# Power.net
KiCad netlist of a schematic drawn in Altium Designer
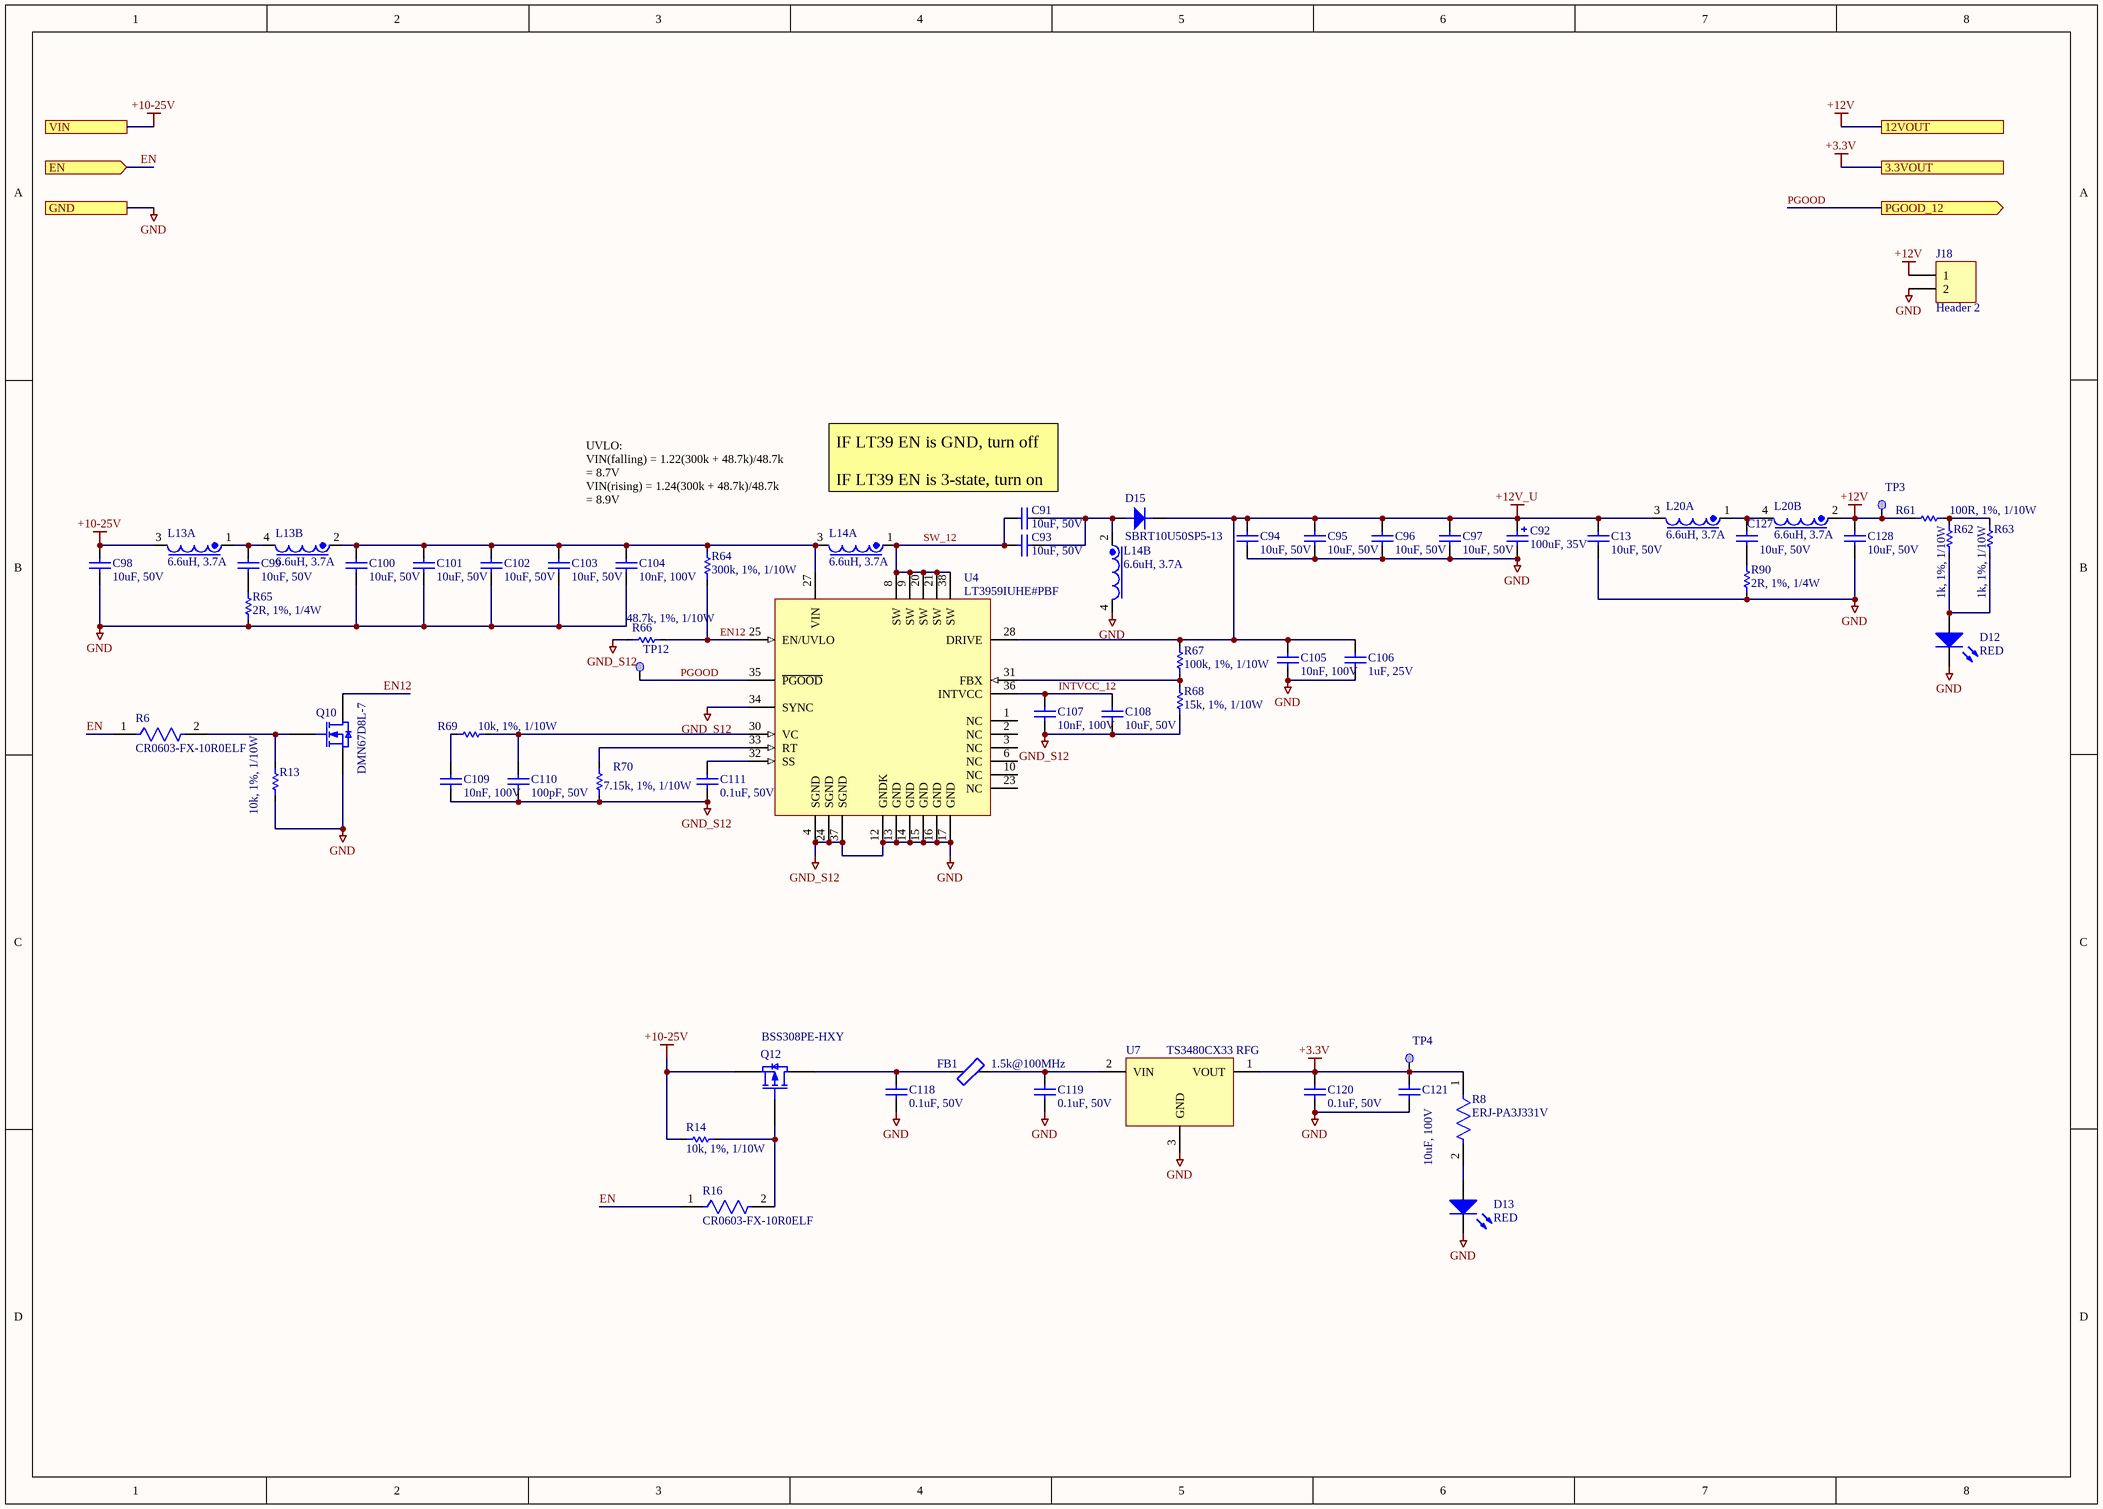
[diagram p0: Power.SchDoc]

(export (version "E")
  (design (tool "Eeschema 10.0.6"))
  (components
    (comp (ref "C13")
      (value "10uF, 50V")
      (footprint "1206")
      (description "CAP CER 10UF 50V X7R 1206")
      (fields (field (name "PART NUMBER") "NS00832"))
      (libsource (lib "FullPartsDB") (part "Cap"))
    )
    (comp (ref "C91")
      (value "10uF, 50V")
      (footprint "1206")
      (description "CAP CER 10UF 50V X7R 1206")
      (fields (field (name "PART NUMBER") "NS00832"))
      (libsource (lib "FullPartsDB") (part "Cap"))
    )
    (comp (ref "C92")
      (value "100uF, 35V")
      (footprint "CAPAE7866X80L")
      (description "CAP ALUM 100UF 20% 35V SMD")
      (fields (field (name "PART NUMBER") "NS00911"))
      (libsource (lib "FullPartsDB") (part "CAP_POL"))
    )
    (comp (ref "C93")
      (value "10uF, 50V")
      (footprint "1206")
      (description "CAP CER 10UF 50V X7R 1206")
      (fields (field (name "PART NUMBER") "NS00832"))
      (libsource (lib "FullPartsDB") (part "Cap"))
    )
    (comp (ref "C94")
      (value "10uF, 50V")
      (footprint "1206")
      (description "CAP CER 10UF 50V X7R 1206")
      (fields (field (name "PART NUMBER") "NS00832"))
      (libsource (lib "FullPartsDB") (part "Cap"))
    )
    (comp (ref "C95")
      (value "10uF, 50V")
      (footprint "1206")
      (description "CAP CER 10UF 50V X7R 1206")
      (fields (field (name "PART NUMBER") "NS00832"))
      (libsource (lib "FullPartsDB") (part "Cap"))
    )
    (comp (ref "C96")
      (value "10uF, 50V")
      (footprint "1206")
      (description "CAP CER 10UF 50V X7R 1206")
      (fields (field (name "PART NUMBER") "NS00832"))
      (libsource (lib "FullPartsDB") (part "Cap"))
    )
    (comp (ref "C97")
      (value "10uF, 50V")
      (footprint "1206")
      (description "CAP CER 10UF 50V X7R 1206")
      (fields (field (name "PART NUMBER") "NS00832"))
      (libsource (lib "FullPartsDB") (part "Cap"))
    )
    (comp (ref "C98")
      (value "10uF, 50V")
      (footprint "1206")
      (description "CAP CER 10UF 50V X7R 1206")
      (fields (field (name "PART NUMBER") "NS00832"))
      (libsource (lib "FullPartsDB") (part "Cap"))
    )
    (comp (ref "C99")
      (value "10uF, 50V")
      (footprint "1206")
      (description "CAP CER 10UF 50V X7R 1206")
      (fields (field (name "PART NUMBER") "NS00832"))
      (libsource (lib "FullPartsDB") (part "Cap"))
    )
    (comp (ref "C100")
      (value "10uF, 50V")
      (footprint "1206")
      (description "CAP CER 10UF 50V X7R 1206")
      (fields (field (name "PART NUMBER") "NS00832"))
      (libsource (lib "FullPartsDB") (part "Cap"))
    )
    (comp (ref "C101")
      (value "10uF, 50V")
      (footprint "1206")
      (description "CAP CER 10UF 50V X7R 1206")
      (fields (field (name "PART NUMBER") "NS00832"))
      (libsource (lib "FullPartsDB") (part "Cap"))
    )
    (comp (ref "C102")
      (value "10uF, 50V")
      (footprint "1206")
      (description "CAP CER 10UF 50V X7R 1206")
      (fields (field (name "PART NUMBER") "NS00832"))
      (libsource (lib "FullPartsDB") (part "Cap"))
    )
    (comp (ref "C103")
      (value "10uF, 50V")
      (footprint "1206")
      (description "CAP CER 10UF 50V X7R 1206")
      (fields (field (name "PART NUMBER") "NS00832"))
      (libsource (lib "FullPartsDB") (part "Cap"))
    )
    (comp (ref "C104")
      (value "10nF, 100V")
      (footprint "0603")
      (description "CAP CER 10000PF 100V C0G 0603")
      (fields (field (name "PART NUMBER") "NS00848"))
      (libsource (lib "FullPartsDB") (part "Cap"))
    )
    (comp (ref "C105")
      (value "10nF, 100V")
      (footprint "0603")
      (description "CAP CER 10000PF 100V C0G 0603")
      (fields (field (name "PART NUMBER") "NS00848"))
      (libsource (lib "FullPartsDB") (part "Cap"))
    )
    (comp (ref "C106")
      (value "1uF, 25V")
      (footprint "0603")
      (description "CAP CER 1UF 25V X7R 0603")
      (fields (field (name "PART NUMBER") "NS00836"))
      (libsource (lib "FullPartsDB") (part "Cap"))
    )
    (comp (ref "C107")
      (value "10nF, 100V")
      (footprint "0603")
      (description "CAP CER 10000PF 100V C0G 0603")
      (fields (field (name "PART NUMBER") "NS00848"))
      (libsource (lib "FullPartsDB") (part "Cap"))
    )
    (comp (ref "C108")
      (value "10uF, 50V")
      (footprint "1206")
      (description "CAP CER 10UF 50V X7R 1206")
      (fields (field (name "PART NUMBER") "NS00832"))
      (libsource (lib "FullPartsDB") (part "Cap"))
    )
    (comp (ref "C109")
      (value "10nF, 100V")
      (footprint "0603")
      (description "CAP CER 10000PF 100V C0G 0603")
      (fields (field (name "PART NUMBER") "NS00848"))
      (libsource (lib "FullPartsDB") (part "Cap"))
    )
    (comp (ref "C110")
      (value "100pF, 50V")
      (footprint "0603")
      (description "CAP CER 100PF 50V C0G/NP0 0603")
      (fields (field (name "PART NUMBER") "NS00840"))
      (libsource (lib "FullPartsDB") (part "Cap"))
    )
    (comp (ref "C111")
      (value "0.1uF, 50V")
      (footprint "0603")
      (description "CAP CER 0.1UF 50V X7R 0603")
      (fields (field (name "PART NUMBER") "NS00838"))
      (libsource (lib "FullPartsDB") (part "Cap"))
    )
    (comp (ref "C118")
      (value "0.1uF, 50V")
      (footprint "0603")
      (description "CAP CER 0.1UF 50V X7R 0603")
      (fields (field (name "PART NUMBER") "NS00838"))
      (libsource (lib "FullPartsDB") (part "Cap"))
    )
    (comp (ref "C119")
      (value "0.1uF, 50V")
      (footprint "0603")
      (description "CAP CER 0.1UF 50V X7R 0603")
      (fields (field (name "PART NUMBER") "NS00838"))
      (libsource (lib "FullPartsDB") (part "Cap"))
    )
    (comp (ref "C120")
      (value "0.1uF, 50V")
      (footprint "0603")
      (description "CAP CER 0.1UF 50V X7R 0603")
      (fields (field (name "PART NUMBER") "NS00838"))
      (libsource (lib "FullPartsDB") (part "Cap"))
    )
    (comp (ref "C121")
      (value "10uF, 100V")
      (footprint "1210")
      (description "MLCC 10UF 100V X7S 1210")
      (fields (field (name "PART NUMBER") "NS00779"))
      (libsource (lib "FullPartsDB") (part "Cap"))
    )
    (comp (ref "C127")
      (value "10uF, 50V")
      (footprint "1206")
      (description "CAP CER 10UF 50V X7R 1206")
      (fields (field (name "PART NUMBER") "NS00832"))
      (libsource (lib "FullPartsDB") (part "Cap"))
    )
    (comp (ref "C128")
      (value "10uF, 50V")
      (footprint "1206")
      (description "CAP CER 10UF 50V X7R 1206")
      (fields (field (name "PART NUMBER") "NS00832"))
      (libsource (lib "FullPartsDB") (part "Cap"))
    )
    (comp (ref "D12")
      (value "RED")
      (footprint "0603_DIODE_K1A2")
      (description "LED RED CLEAR 1608 SMD")
      (fields (field (name "PART NUMBER") "NS00945"))
      (libsource (lib "FullPartsDB") (part "LED_K1A2"))
    )
    (comp (ref "D13")
      (value "RED")
      (footprint "0603_DIODE_K1A2")
      (description "LED RED CLEAR 1608 SMD")
      (fields (field (name "PART NUMBER") "NS00945"))
      (libsource (lib "FullPartsDB") (part "LED_K1A2"))
    )
    (comp (ref "D15")
      (value "SBRT10U50SP5-13")
      (footprint "DPAK184P650X115-3L")
      (description "DIODE SBR 50V 10A POWERDI5")
      (fields (field (name "PART NUMBER") "NS00833"))
      (libsource (lib "FullPartsDB") (part "Diode"))
    )
    (comp (ref "FB1")
      (value "1.5k@100MHz")
      (footprint "0805")
      (description "WE-CBA SMT EMI SUPPRESSION FERRITE")
      (fields (field (name "PART NUMBER") "NS00881"))
      (libsource (lib "FullPartsDB") (part "Bead"))
    )
    (comp (ref "J18")
      (value "Header 2")
      (footprint "CONN-TH_2P-P2.50_HX25003-2A")
      (description "Header, 2-Pin")
      (fields (field (name "PUBLISHER") "Altium Limited"))
      (libsource (lib "Miscellaneous Connectors") (part "Header 2"))
    )
    (comp (ref "L13")
      (value "6.6uH, 3.7A")
      (footprint "PLCC300P1250X1250X600-4N")
      (description "INDUCT ARRAY 2 COIL 6.6UH SMD")
      (fields (field (name "PART NUMBER") "NS00831"))
      (libsource (lib "FullPartsDB") (part "Inductor_Array_2_13_24"))
    )
    (comp (ref "L14")
      (value "6.6uH, 3.7A")
      (footprint "PLCC300P1250X1250X600-4N")
      (description "INDUCT ARRAY 2 COIL 6.6UH SMD")
      (fields (field (name "PART NUMBER") "NS00831"))
      (libsource (lib "FullPartsDB") (part "Inductor_Array_2_13_24"))
    )
    (comp (ref "L20")
      (value "6.6uH, 3.7A")
      (footprint "PLCC300P1250X1250X600-4N")
      (description "INDUCT ARRAY 2 COIL 6.6UH SMD")
      (fields (field (name "PART NUMBER") "NS00831"))
      (libsource (lib "") (part "Inductor_Array_2_13_24_1"))
    )
    (comp (ref "Q10")
      (value "DMN67D8L-7")
      (footprint "SOT23-3")
      (description "MOSFET N-CH 60V 210MA SOT23")
      (fields (field (name "PART NUMBER") "NS00873") (field (name "PUBLISHER") "Altium Limited"))
      (libsource (lib "FullPartsDB") (part "FET_N_GSD"))
    )
    (comp (ref "Q12")
      (value "BSS308PE-HXY")
      (footprint "SOT23-3")
      (description "P-CHANNEL MOSFET")
      (fields (field (name "PART NUMBER") "NS00810"))
      (libsource (lib "FullPartsDB") (part "FET_P_GDS"))
    )
    (comp (ref "R6")
      (value "CR0603-FX-10R0ELF")
      (footprint "FP-CR0603-MFG")
      (description "Thick Film Chip Resistors 0603 10Ω 0.1W 1% 100ppm/°C")
      (fields (field (name "TOLERANCE") "1%"))
      (libsource (lib "Altium Content Vault") (part "1029c3af85768c4190bb7ad29bc67b5"))
    )
    (comp (ref "R8")
      (value "ERJ-PA3J331V")
      (footprint "FP-ERJPA3-MFG")
      (description "RES SMD 330 OHM 5% 1/4W 0603")
      (fields (field (name "TOLERANCE") "5%"))
      (libsource (lib "Altium Content Vault") (part "1029c3af85768c4190bb7ad29bc67b5"))
    )
    (comp (ref "R13")
      (value "10k, 1%, 1/10W")
      (footprint "0603")
      (description "RES 10K OHM 1% 1/10W 0603")
      (fields (field (name "PART NUMBER") "NS00820"))
      (libsource (lib "FullPartsDB") (part "RESISTOR"))
    )
    (comp (ref "R14")
      (value "10k, 1%, 1/10W")
      (footprint "0603")
      (description "RES 10K OHM 1% 1/10W 0603")
      (fields (field (name "PART NUMBER") "NS00820"))
      (libsource (lib "FullPartsDB") (part "RESISTOR"))
    )
    (comp (ref "R16")
      (value "CR0603-FX-10R0ELF")
      (footprint "FP-CR0603-MFG")
      (description "Thick Film Chip Resistors 0603 10Ω 0.1W 1% 100ppm/°C")
      (fields (field (name "TOLERANCE") "1%"))
      (libsource (lib "Altium Content Vault") (part "1029c3af85768c4190bb7ad29bc67b5"))
    )
    (comp (ref "R61")
      (value "100R, 1%, 1/10W")
      (footprint "0603")
      (description "RES 100 OHM 1% 1/10W 0603")
      (fields (field (name "PART NUMBER") "NS00870"))
      (libsource (lib "FullPartsDB") (part "RESISTOR"))
    )
    (comp (ref "R62")
      (value "1k, 1%, 1/10W")
      (footprint "0603")
      (description "RES 1K OHM 1% 1/10W 0603")
      (fields (field (name "PART NUMBER") "NS00882"))
      (libsource (lib "FullPartsDB") (part "RESISTOR"))
    )
    (comp (ref "R63")
      (value "1k, 1%, 1/10W")
      (footprint "0603")
      (description "RES 1K OHM 1% 1/10W 0603")
      (fields (field (name "PART NUMBER") "NS00882"))
      (libsource (lib "FullPartsDB") (part "RESISTOR"))
    )
    (comp (ref "R64")
      (value "300k, 1%, 1/10W")
      (footprint "0603")
      (description "RES 300K OHM 1% 1/10W 0603")
      (fields (field (name "PART NUMBER") "NS00837"))
      (libsource (lib "FullPartsDB") (part "RESISTOR"))
    )
    (comp (ref "R65")
      (value "2R, 1%, 1/4W")
      (footprint "1206")
      (description "RES 2 OHM 1% 1/4W 1206")
      (fields (field (name "PART NUMBER") "NS00946"))
      (libsource (lib "FullPartsDB") (part "RESISTOR"))
    )
    (comp (ref "R66")
      (value "48.7k, 1%, 1/10W")
      (footprint "0603")
      (description "RES 48.7K OHM 1% 1/10W 0603")
      (fields (field (name "PART NUMBER") "NS00826"))
      (libsource (lib "FullPartsDB") (part "RESISTOR"))
    )
    (comp (ref "R67")
      (value "100k, 1%, 1/10W")
      (footprint "0603")
      (description "RES 100K OHM 1% 1/10W 0603")
      (fields (field (name "PART NUMBER") "NS00835"))
      (libsource (lib "FullPartsDB") (part "RESISTOR"))
    )
    (comp (ref "R68")
      (value "15k, 1%, 1/10W")
      (footprint "0603")
      (description "RES 15K OHM 1% 1/10W 0603")
      (fields (field (name "PART NUMBER") "NS00834"))
      (libsource (lib "FullPartsDB") (part "RESISTOR"))
    )
    (comp (ref "R69")
      (value "10k, 1%, 1/10W")
      (footprint "0603")
      (description "RES 10K OHM 1% 1/10W 0603")
      (fields (field (name "PART NUMBER") "NS00820"))
      (libsource (lib "FullPartsDB") (part "RESISTOR"))
    )
    (comp (ref "R70")
      (value "7.15k, 1%, 1/10W")
      (footprint "0603")
      (description "RES 7.15K OHM 1% 1/10W 0603")
      (fields (field (name "PART NUMBER") "NS00839"))
      (libsource (lib "FullPartsDB") (part "RESISTOR"))
    )
    (comp (ref "R90")
      (value "2R, 1%, 1/4W")
      (footprint "1206")
      (description "RES 2 OHM 1% 1/4W 1206")
      (fields (field (name "PART NUMBER") "NS00946"))
      (libsource (lib "FullPartsDB") (part "RESISTOR"))
    )
    (comp (ref "TP3")
      (value "Test Point")
      (footprint "TEST POINT 40 Mil")
      (description "Test Point 0.3mm")
      (libsource (lib "1_EverythingElse") (part "Test Point"))
    )
    (comp (ref "TP4")
      (value "Test Point")
      (footprint "TEST POINT 40 Mil")
      (description "Test Point 0.3mm")
      (libsource (lib "1_EverythingElse") (part "Test Point"))
    )
    (comp (ref "TP12")
      (value "Test Point")
      (footprint "TEST POINT 40 Mil")
      (description "Test Point 0.3mm")
      (libsource (lib "1_EverythingElse") (part "Test Point"))
    )
    (comp (ref "U4")
      (value "LT3959IUHE#PBF")
      (footprint "QFN50P500X600X80_LT_UHEMA")
      (description "IC REG MULTI CONFG ADJ 6A 36QFN")
      (fields (field (name "PART NUMBER") "NS00829"))
      (libsource (lib "FullPartsDB") (part "LINEAR_LTC3959-UHEMA"))
    )
    (comp (ref "U7")
      (value "TS3480CX33 RFG")
      (footprint "SOT23-3")
      (description "IC REG LINEAR 3.3V 100MA SOT23")
      (fields (field (name "PART NUMBER") "NS00929"))
      (libsource (lib "FullPartsDB") (part "VREG_FIXED_OIG"))
    )
  )
  (nets
    (net (code "1") (name "+3.3V") (class "Default")
      (node (ref "C120") (pin "1") (pinfunction "1_1") (pintype "passive"))
      (node (ref "C121") (pin "2") (pinfunction "2_2") (pintype "passive"))
      (node (ref "R8") (pin "1") (pinfunction "1_1") (pintype "passive"))
      (node (ref "TP4") (pin "1") (pinfunction "1_1") (pintype "passive"))
      (node (ref "U7") (pin "1") (pinfunction "VOUT_1") (pintype "power_in"))
    )
    (net (code "2") (name "+10-25V") (class "Default")
      (node (ref "C98") (pin "2") (pinfunction "2_2") (pintype "passive"))
      (node (ref "L13") (pin "3") (pinfunction "2_3") (pintype "passive"))
      (node (ref "Q12") (pin "3") (pinfunction "S_3") (pintype "passive"))
      (node (ref "R14") (pin "1") (pinfunction "1_1") (pintype "passive"))
    )
    (net (code "3") (name "+12V") (class "Default")
      (node (ref "C128") (pin "2") (pinfunction "2_2") (pintype "passive"))
      (node (ref "J18") (pin "1") (pinfunction "1_1") (pintype "passive"))
      (node (ref "L20") (pin "2") (pinfunction "3_2") (pintype "passive"))
      (node (ref "R61") (pin "2") (pinfunction "2_2") (pintype "passive"))
      (node (ref "TP3") (pin "1") (pinfunction "1_1") (pintype "passive"))
    )
    (net (code "4") (name "+12V_U") (class "Default")
      (node (ref "C105") (pin "2") (pinfunction "2_2") (pintype "passive"))
      (node (ref "C106") (pin "2") (pinfunction "2_2") (pintype "passive"))
      (node (ref "C13") (pin "2") (pinfunction "2_2") (pintype "passive"))
      (node (ref "C92") (pin "1") (pinfunction "1_1") (pintype "passive"))
      (node (ref "C94") (pin "2") (pinfunction "2_2") (pintype "passive"))
      (node (ref "C95") (pin "2") (pinfunction "2_2") (pintype "passive"))
      (node (ref "C96") (pin "2") (pinfunction "2_2") (pintype "passive"))
      (node (ref "C97") (pin "2") (pinfunction "2_2") (pintype "passive"))
      (node (ref "D15") (pin "2") (pinfunction "K_2") (pintype "passive"))
      (node (ref "L20") (pin "3") (pinfunction "2_3") (pintype "passive"))
      (node (ref "R67") (pin "2") (pinfunction "2_2") (pintype "passive"))
      (node (ref "U4") (pin "28") (pinfunction "DRIVE_28") (pintype "power_in"))
    )
    (net (code "5") (name "/EN") (class "Default")
      (node (ref "R16") (pin "1") (pinfunction "1_1") (pintype "passive"))
      (node (ref "R6") (pin "1") (pinfunction "1_1") (pintype "passive"))
    )
    (net (code "6") (name "/EN12") (class "Default")
      (node (ref "Q10") (pin "3") (pinfunction "D_3") (pintype "passive"))
      (node (ref "R64") (pin "1") (pinfunction "1_1") (pintype "passive"))
      (node (ref "R66") (pin "1") (pinfunction "1_1") (pintype "passive"))
      (node (ref "U4") (pin "25") (pinfunction "EN/UVLO_25") (pintype "input"))
    )
    (net (code "7") (name "/INTVCC_12") (class "Default")
      (node (ref "C107") (pin "2") (pinfunction "2_2") (pintype "passive"))
      (node (ref "C108") (pin "2") (pinfunction "2_2") (pintype "passive"))
      (node (ref "U4") (pin "36") (pinfunction "INTVCC_36") (pintype "power_in"))
    )
    (net (code "8") (name "/PGOOD") (class "Default")
      (node (ref "TP12") (pin "1") (pinfunction "1_1") (pintype "passive"))
      (node (ref "U4") (pin "35") (pinfunction "PGOOD_35") (pintype "open_collector"))
    )
    (net (code "9") (name "/SW_12") (class "Default")
      (node (ref "C91") (pin "1") (pinfunction "1_1") (pintype "passive"))
      (node (ref "C93") (pin "1") (pinfunction "1_1") (pintype "passive"))
      (node (ref "L14") (pin "1") (pinfunction "1_1") (pintype "passive"))
      (node (ref "U4") (pin "20") (pinfunction "SW_20") (pintype "open_collector"))
      (node (ref "U4") (pin "21") (pinfunction "SW_21") (pintype "open_collector"))
      (node (ref "U4") (pin "38") (pinfunction "SW_38") (pintype "open_collector"))
      (node (ref "U4") (pin "8") (pinfunction "SW_8") (pintype "open_collector"))
      (node (ref "U4") (pin "9") (pinfunction "SW_9") (pintype "open_collector"))
    )
    (net (code "10") (name "GND") (class "Default")
      (node (ref "C100") (pin "1") (pinfunction "1_1") (pintype "passive"))
      (node (ref "C101") (pin "1") (pinfunction "1_1") (pintype "passive"))
      (node (ref "C102") (pin "1") (pinfunction "1_1") (pintype "passive"))
      (node (ref "C103") (pin "1") (pinfunction "1_1") (pintype "passive"))
      (node (ref "C104") (pin "1") (pinfunction "1_1") (pintype "passive"))
      (node (ref "C105") (pin "1") (pinfunction "1_1") (pintype "passive"))
      (node (ref "C106") (pin "1") (pinfunction "1_1") (pintype "passive"))
      (node (ref "C107") (pin "1") (pinfunction "1_1") (pintype "passive"))
      (node (ref "C108") (pin "1") (pinfunction "1_1") (pintype "passive"))
      (node (ref "C109") (pin "1") (pinfunction "1_1") (pintype "passive"))
      (node (ref "C110") (pin "1") (pinfunction "1_1") (pintype "passive"))
      (node (ref "C111") (pin "2") (pinfunction "2_2") (pintype "passive"))
      (node (ref "C118") (pin "2") (pinfunction "2_2") (pintype "passive"))
      (node (ref "C119") (pin "2") (pinfunction "2_2") (pintype "passive"))
      (node (ref "C120") (pin "2") (pinfunction "2_2") (pintype "passive"))
      (node (ref "C121") (pin "1") (pinfunction "1_1") (pintype "passive"))
      (node (ref "C128") (pin "1") (pinfunction "1_1") (pintype "passive"))
      (node (ref "C13") (pin "1") (pinfunction "1_1") (pintype "passive"))
      (node (ref "C92") (pin "2") (pinfunction "2_2") (pintype "passive"))
      (node (ref "C94") (pin "1") (pinfunction "1_1") (pintype "passive"))
      (node (ref "C95") (pin "1") (pinfunction "1_1") (pintype "passive"))
      (node (ref "C96") (pin "1") (pinfunction "1_1") (pintype "passive"))
      (node (ref "C97") (pin "1") (pinfunction "1_1") (pintype "passive"))
      (node (ref "C98") (pin "1") (pinfunction "1_1") (pintype "passive"))
      (node (ref "D12") (pin "2") (pinfunction "K_2") (pintype "passive"))
      (node (ref "D13") (pin "2") (pinfunction "K_2") (pintype "passive"))
      (node (ref "J18") (pin "2") (pinfunction "2_2") (pintype "passive"))
      (node (ref "L14") (pin "4") (pinfunction "4_4") (pintype "passive"))
      (node (ref "Q10") (pin "2") (pinfunction "S_2") (pintype "passive"))
      (node (ref "R13") (pin "2") (pinfunction "2_2") (pintype "passive"))
      (node (ref "R65") (pin "1") (pinfunction "1_1") (pintype "passive"))
      (node (ref "R66") (pin "2") (pinfunction "2_2") (pintype "passive"))
      (node (ref "R68") (pin "1") (pinfunction "1_1") (pintype "passive"))
      (node (ref "R70") (pin "1") (pinfunction "1_1") (pintype "passive"))
      (node (ref "R90") (pin "1") (pinfunction "1_1") (pintype "passive"))
      (node (ref "U4") (pin "12") (pinfunction "GNDK_12") (pintype "power_in"))
      (node (ref "U4") (pin "13") (pinfunction "GND_13") (pintype "power_in"))
      (node (ref "U4") (pin "14") (pinfunction "GND_14") (pintype "power_in"))
      (node (ref "U4") (pin "15") (pinfunction "GND_15") (pintype "power_in"))
      (node (ref "U4") (pin "16") (pinfunction "GND_16") (pintype "power_in"))
      (node (ref "U4") (pin "17") (pinfunction "GND_17") (pintype "power_in"))
      (node (ref "U4") (pin "24") (pinfunction "SGND_24") (pintype "power_in"))
      (node (ref "U4") (pin "34") (pinfunction "SYNC_34") (pintype "power_in"))
      (node (ref "U4") (pin "37") (pinfunction "SGND_37") (pintype "power_in"))
      (node (ref "U4") (pin "4") (pinfunction "SGND_4") (pintype "power_in"))
      (node (ref "U7") (pin "3") (pinfunction "GND_3") (pintype "power_in"))
    )
    (net (code "11") (name "Net-(C99-Pad1)") (class "Default")
      (node (ref "C99") (pin "1") (pinfunction "1_1") (pintype "passive"))
      (node (ref "R65") (pin "2") (pinfunction "2_2") (pintype "passive"))
    )
    (net (code "12") (name "Net-(C99-Pad2)") (class "Default")
      (node (ref "C99") (pin "2") (pinfunction "2_2") (pintype "passive"))
      (node (ref "L13") (pin "1") (pinfunction "1_1") (pintype "passive"))
      (node (ref "L13") (pin "4") (pinfunction "4_4") (pintype "passive"))
    )
    (net (code "13") (name "Net-(C109-Pad2)") (class "Default")
      (node (ref "C109") (pin "2") (pinfunction "2_2") (pintype "passive"))
      (node (ref "R69") (pin "2") (pinfunction "2_2") (pintype "passive"))
    )
    (net (code "14") (name "Net-(C127-Pad1)") (class "Default")
      (node (ref "C127") (pin "1") (pinfunction "1_1") (pintype "passive"))
      (node (ref "R90") (pin "2") (pinfunction "2_2") (pintype "passive"))
    )
    (net (code "15") (name "Net-(C127-Pad2)") (class "Default")
      (node (ref "C127") (pin "2") (pinfunction "2_2") (pintype "passive"))
      (node (ref "L20") (pin "1") (pinfunction "1_1") (pintype "passive"))
      (node (ref "L20") (pin "4") (pinfunction "4_4") (pintype "passive"))
    )
    (net (code "16") (name "Net-(D12-A)") (class "Default")
      (node (ref "D12") (pin "1") (pinfunction "A_1") (pintype "passive"))
      (node (ref "R62") (pin "2") (pinfunction "2_2") (pintype "passive"))
      (node (ref "R63") (pin "2") (pinfunction "2_2") (pintype "passive"))
    )
    (net (code "17") (name "Net-(D13-A)") (class "Default")
      (node (ref "D13") (pin "1") (pinfunction "A_1") (pintype "passive"))
      (node (ref "R8") (pin "2") (pinfunction "2_2") (pintype "passive"))
    )
    (net (code "18") (name "Net-(D15-A)") (class "Default")
      (node (ref "C91") (pin "2") (pinfunction "2_2") (pintype "passive"))
      (node (ref "C93") (pin "2") (pinfunction "2_2") (pintype "passive"))
      (node (ref "D15") (pin "1") (pinfunction "A_1") (pintype "passive"))
      (node (ref "L14") (pin "2") (pinfunction "3_2") (pintype "passive"))
    )
    (net (code "19") (name "Net-(L13B-3)") (class "Default")
      (node (ref "C100") (pin "2") (pinfunction "2_2") (pintype "passive"))
      (node (ref "C101") (pin "2") (pinfunction "2_2") (pintype "passive"))
      (node (ref "C102") (pin "2") (pinfunction "2_2") (pintype "passive"))
      (node (ref "C103") (pin "2") (pinfunction "2_2") (pintype "passive"))
      (node (ref "C104") (pin "2") (pinfunction "2_2") (pintype "passive"))
      (node (ref "L13") (pin "2") (pinfunction "3_2") (pintype "passive"))
      (node (ref "L14") (pin "3") (pinfunction "2_3") (pintype "passive"))
      (node (ref "R64") (pin "2") (pinfunction "2_2") (pintype "passive"))
      (node (ref "U4") (pin "27") (pinfunction "VIN_27") (pintype "power_in"))
    )
    (net (code "20") (name "Net-(Q10-G)") (class "Default")
      (node (ref "Q10") (pin "1") (pinfunction "G_1") (pintype "passive"))
      (node (ref "R13") (pin "1") (pinfunction "1_1") (pintype "passive"))
      (node (ref "R6") (pin "2") (pinfunction "2_2") (pintype "passive"))
    )
    (net (code "21") (name "Net-(Q12-D)") (class "Default")
      (node (ref "C118") (pin "1") (pinfunction "1_1") (pintype "passive"))
      (node (ref "FB1") (pin "1") (pinfunction "1_1") (pintype "passive"))
      (node (ref "Q12") (pin "2") (pinfunction "D_2") (pintype "passive"))
    )
    (net (code "22") (name "Net-(Q12-G)") (class "Default")
      (node (ref "Q12") (pin "1") (pinfunction "G_1") (pintype "passive"))
      (node (ref "R14") (pin "2") (pinfunction "2_2") (pintype "passive"))
      (node (ref "R16") (pin "2") (pinfunction "2_2") (pintype "passive"))
    )
    (net (code "23") (name "Net-(R61-Pad1)") (class "Default")
      (node (ref "R61") (pin "1") (pinfunction "1_1") (pintype "passive"))
      (node (ref "R62") (pin "1") (pinfunction "1_1") (pintype "passive"))
      (node (ref "R63") (pin "1") (pinfunction "1_1") (pintype "passive"))
    )
    (net (code "24") (name "Net-(U4-FBX)") (class "Default")
      (node (ref "R67") (pin "1") (pinfunction "1_1") (pintype "passive"))
      (node (ref "R68") (pin "2") (pinfunction "2_2") (pintype "passive"))
      (node (ref "U4") (pin "31") (pinfunction "FBX_31") (pintype "input"))
    )
    (net (code "25") (name "Net-(U4-RT)") (class "Default")
      (node (ref "R70") (pin "2") (pinfunction "2_2") (pintype "passive"))
      (node (ref "U4") (pin "33") (pinfunction "RT_33") (pintype "input"))
    )
    (net (code "26") (name "Net-(U4-SS)") (class "Default")
      (node (ref "C111") (pin "1") (pinfunction "1_1") (pintype "passive"))
      (node (ref "U4") (pin "32") (pinfunction "SS_32") (pintype "input"))
    )
    (net (code "27") (name "Net-(U4-VC)") (class "Default")
      (node (ref "C110") (pin "2") (pinfunction "2_2") (pintype "passive"))
      (node (ref "R69") (pin "1") (pinfunction "1_1") (pintype "passive"))
      (node (ref "U4") (pin "30") (pinfunction "VC_30") (pintype "input"))
    )
    (net (code "28") (name "Net-(U7-VIN)") (class "Default")
      (node (ref "C119") (pin "1") (pinfunction "1_1") (pintype "passive"))
      (node (ref "FB1") (pin "2") (pinfunction "2_2") (pintype "passive"))
      (node (ref "U7") (pin "2") (pinfunction "VIN_2") (pintype "power_in"))
    )
    (net (code "29") (name "unconnected-(U4-NC-Pad1)") (class "Default")
      (node (ref "U4") (pin "1") (pinfunction "NC_1") (pintype "passive"))
    )
    (net (code "30") (name "unconnected-(U4-NC-Pad2)") (class "Default")
      (node (ref "U4") (pin "2") (pinfunction "NC_2") (pintype "passive"))
    )
    (net (code "31") (name "unconnected-(U4-NC-Pad3)") (class "Default")
      (node (ref "U4") (pin "3") (pinfunction "NC_3") (pintype "passive"))
    )
    (net (code "32") (name "unconnected-(U4-NC-Pad6)") (class "Default")
      (node (ref "U4") (pin "6") (pinfunction "NC_6") (pintype "passive"))
    )
    (net (code "33") (name "unconnected-(U4-NC-Pad10)") (class "Default")
      (node (ref "U4") (pin "10") (pinfunction "NC_10") (pintype "passive"))
    )
    (net (code "34") (name "unconnected-(U4-NC-Pad23)") (class "Default")
      (node (ref "U4") (pin "23") (pinfunction "NC_23") (pintype "passive"))
    )
  )
)
